# Astable_multivibrator_2021-06-04.net
KiCad netlist of a schematic drawn in EasyEDA
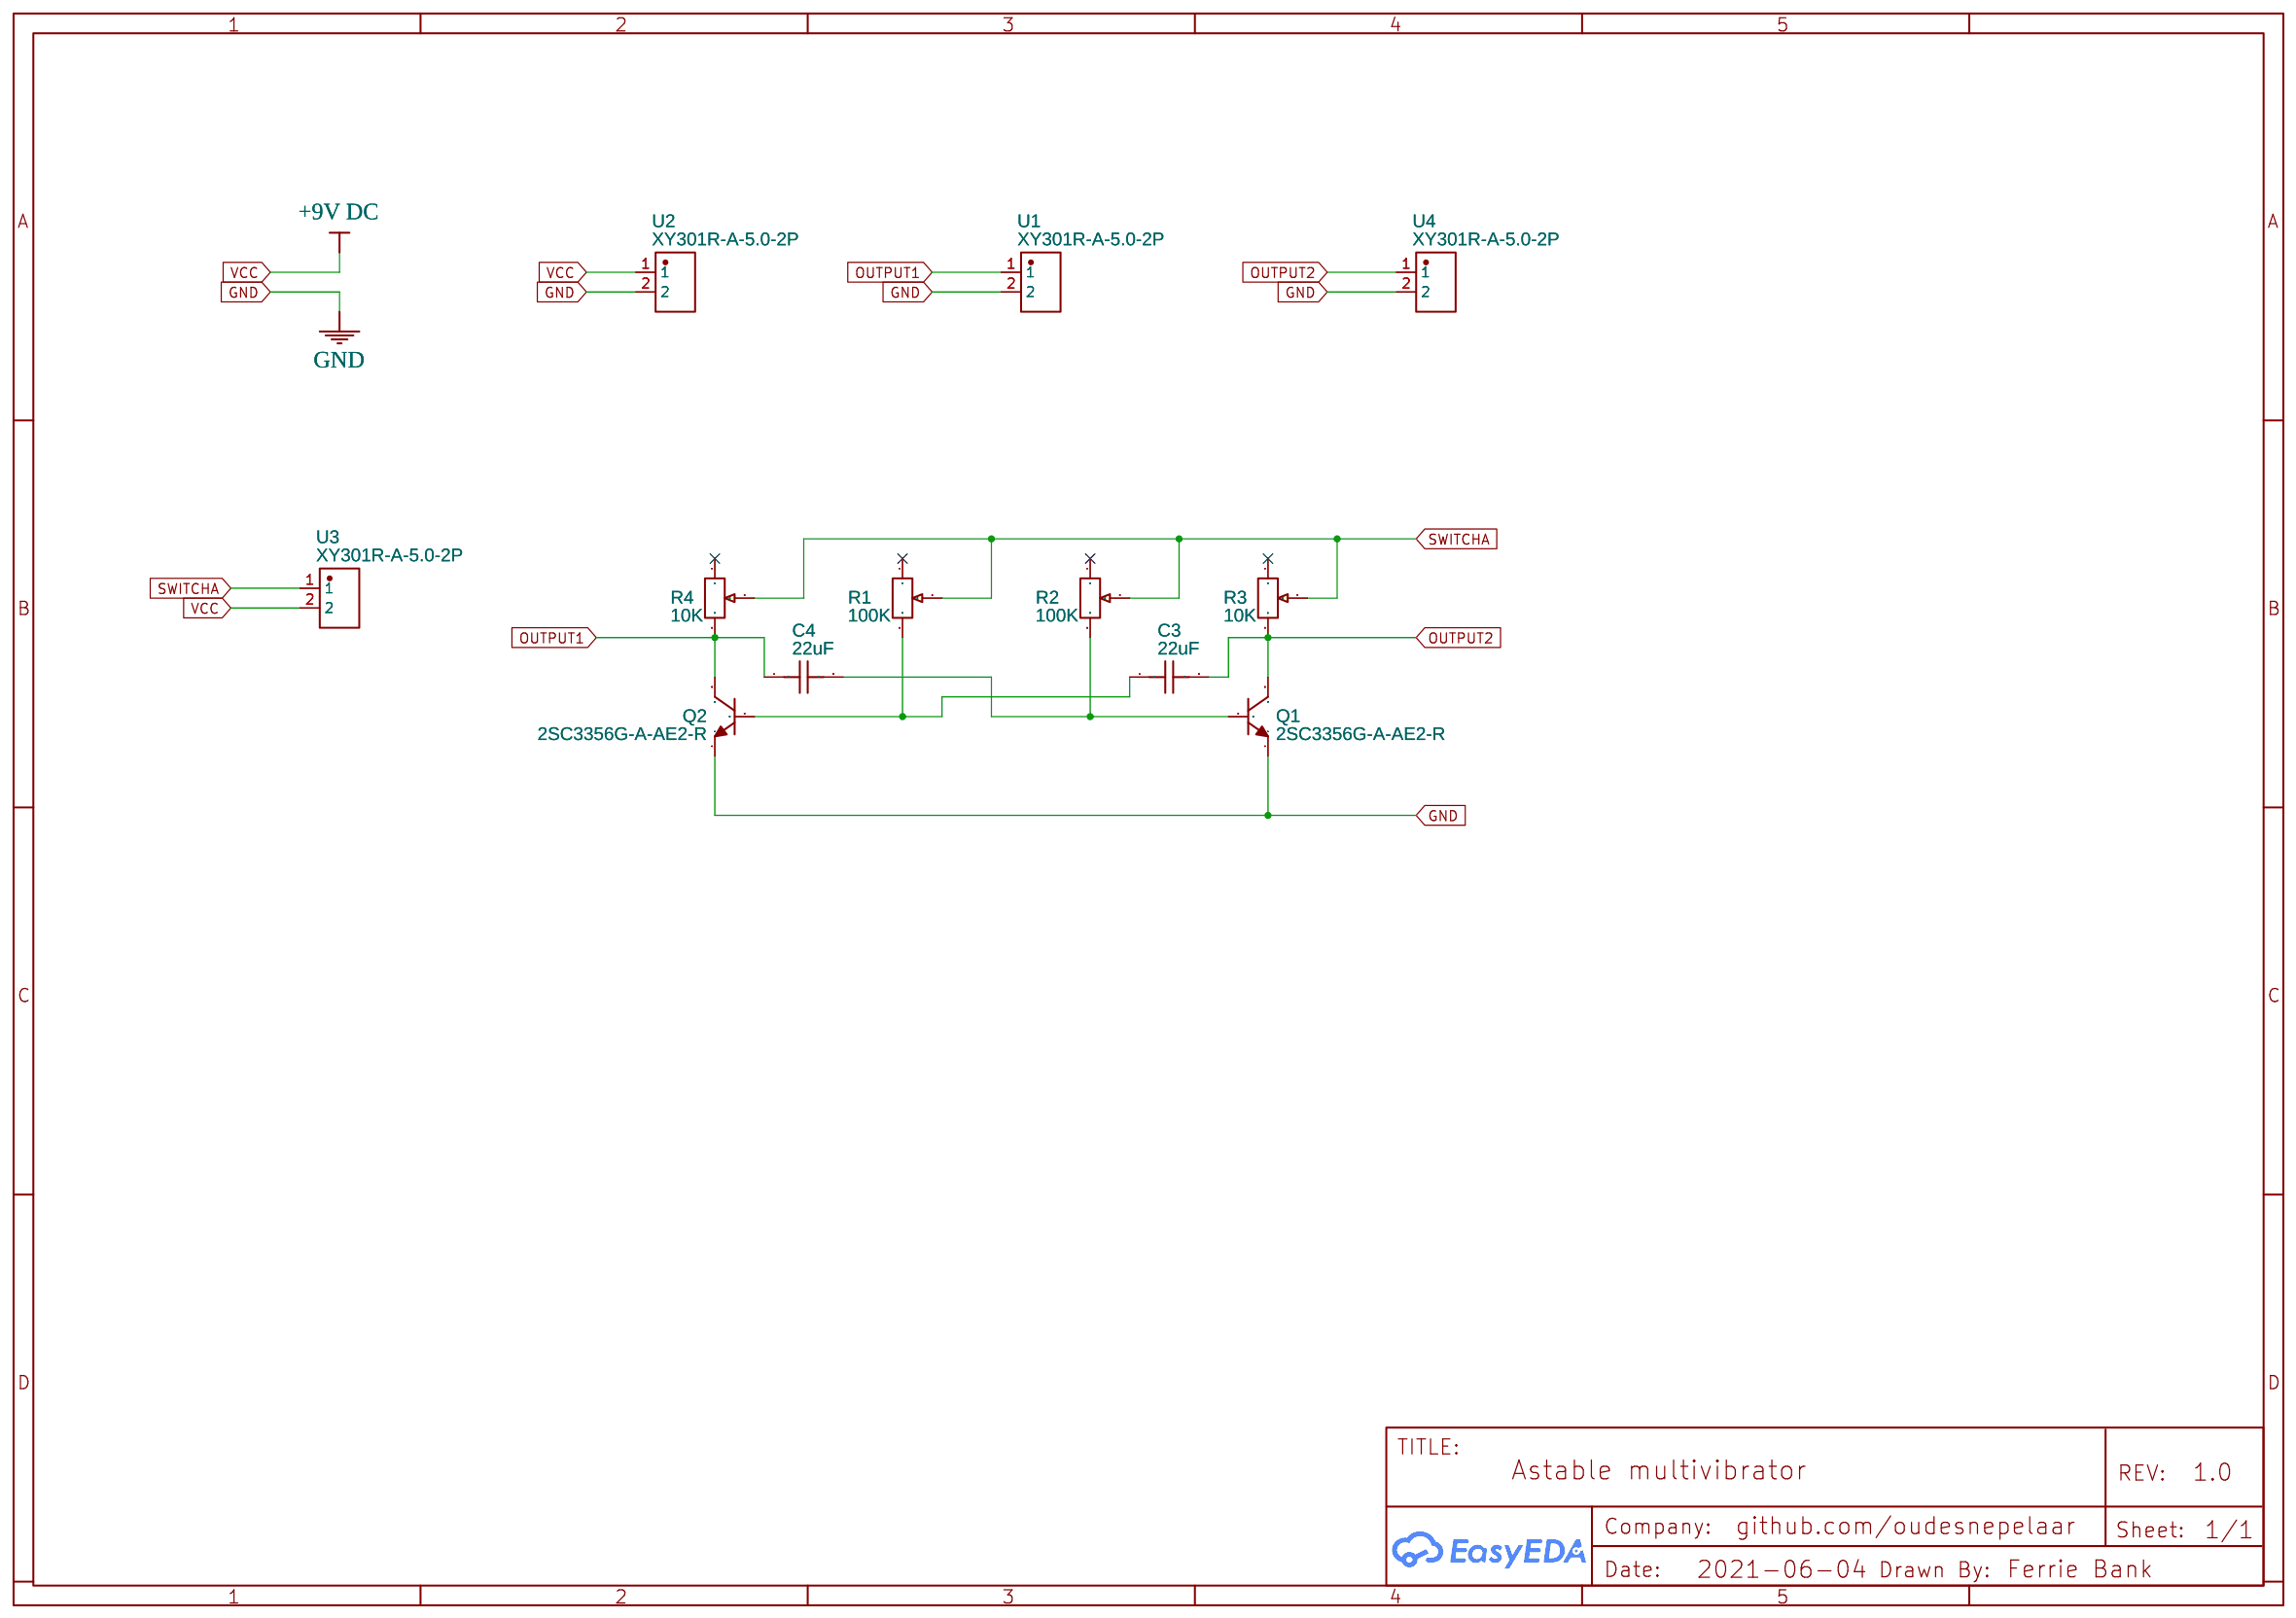
[diagram p0: schematic sheet]

(export (version "E")
  (design (tool "Eeschema 10.0.6"))
  (components
    (comp (ref "C3")
      (value "22uF")
      (fields
        (field (name "BOM_Manufacturer Part") "GRM21BC81C226ME44L")
        (field (name "BOM_Supplier Part") "C258782")
      )
      (libsource (lib "") (part "GRM21BC81C226ME44L"))
    )
    (comp (ref "C4")
      (value "22uF")
      (fields
        (field (name "BOM_Manufacturer Part") "GRM21BC81C226ME44L")
        (field (name "BOM_Supplier Part") "C258782")
      )
      (libsource (lib "") (part "GRM21BC81C226ME44L"))
    )
    (comp (ref "Q1")
      (value "2SC3356G-A-AE2-R")
      (fields (field (name "BOM_Supplier Part") "C171546"))
      (libsource (lib "") (part "2SC3356G-A-AE2-R_1"))
    )
    (comp (ref "Q2")
      (value "2SC3356G-A-AE2-R")
      (fields (field (name "BOM_Supplier Part") "C171546"))
      (libsource (lib "") (part "2SC3356G-A-AE2-R"))
    )
    (comp (ref "R1")
      (value "100K")
      (fields (field (name "BOM_Supplier Part") "C132883"))
      (libsource (lib "") (part "ST-4ETG 100K OHM (104)"))
    )
    (comp (ref "R2")
      (value "100K")
      (fields (field (name "BOM_Supplier Part") "C132883"))
      (libsource (lib "") (part "ST-4ETG 100K OHM (104)"))
    )
    (comp (ref "R3")
      (value "10K")
      (fields (field (name "BOM_Supplier Part") "C132882"))
      (libsource (lib "") (part "ST-4ETG 10K OHM (103)"))
    )
    (comp (ref "R4")
      (value "10K")
      (fields (field (name "BOM_Supplier Part") "C132882"))
      (libsource (lib "") (part "ST-4ETG 10K OHM (103)"))
    )
    (comp (ref "U1")
      (value "XY301R-A-5.0-2P")
      (fields (field (name "BOM_Supplier Part") "C557653"))
      (libsource (lib "") (part "XY301R-A-5.0-2P"))
    )
    (comp (ref "U2")
      (value "XY301R-A-5.0-2P")
      (fields (field (name "BOM_Supplier Part") "C557653"))
      (libsource (lib "") (part "XY301R-A-5.0-2P"))
    )
    (comp (ref "U3")
      (value "XY301R-A-5.0-2P")
      (fields (field (name "BOM_Supplier Part") "C557653"))
      (libsource (lib "") (part "XY301R-A-5.0-2P"))
    )
    (comp (ref "U4")
      (value "XY301R-A-5.0-2P")
      (fields (field (name "BOM_Supplier Part") "C557653"))
      (libsource (lib "") (part "XY301R-A-5.0-2P"))
    )
  )
  (nets
    (net (code "1") (name "GND") (class "Default")
      (node (ref "Q1") (pin "1") (pinfunction "E_1") (pintype "input"))
      (node (ref "Q2") (pin "1") (pinfunction "E_1") (pintype "input"))
      (node (ref "U1") (pin "2") (pinfunction "2_2") (pintype "unspecified"))
      (node (ref "U2") (pin "2") (pinfunction "2_2") (pintype "unspecified"))
      (node (ref "U4") (pin "2") (pinfunction "2_2") (pintype "unspecified"))
    )
    (net (code "2") (name "Net-(Q1-B)") (class "Default")
      (node (ref "C4") (pin "2") (pinfunction "2_2") (pintype "unspecified"))
      (node (ref "Q1") (pin "2") (pinfunction "B_2") (pintype "input"))
      (node (ref "R2") (pin "3") (pinfunction "3_3") (pintype "input"))
    )
    (net (code "3") (name "Net-(Q2-B)") (class "Default")
      (node (ref "C3") (pin "1") (pinfunction "1_1") (pintype "unspecified"))
      (node (ref "Q2") (pin "2") (pinfunction "B_2") (pintype "input"))
      (node (ref "R1") (pin "3") (pinfunction "3_3") (pintype "input"))
    )
    (net (code "4") (name "OUTPUT1") (class "Default")
      (node (ref "C4") (pin "1") (pinfunction "1_1") (pintype "unspecified"))
      (node (ref "Q2") (pin "3") (pinfunction "C_3") (pintype "input"))
      (node (ref "R4") (pin "3") (pinfunction "3_3") (pintype "input"))
      (node (ref "U1") (pin "1") (pinfunction "1_1") (pintype "unspecified"))
    )
    (net (code "5") (name "OUTPUT2") (class "Default")
      (node (ref "C3") (pin "2") (pinfunction "2_2") (pintype "unspecified"))
      (node (ref "Q1") (pin "3") (pinfunction "C_3") (pintype "input"))
      (node (ref "R3") (pin "3") (pinfunction "3_3") (pintype "input"))
      (node (ref "U4") (pin "1") (pinfunction "1_1") (pintype "unspecified"))
    )
    (net (code "6") (name "SWITCHA") (class "Default")
      (node (ref "R1") (pin "2") (pinfunction "2_2") (pintype "input"))
      (node (ref "R2") (pin "2") (pinfunction "2_2") (pintype "input"))
      (node (ref "R3") (pin "2") (pinfunction "2_2") (pintype "input"))
      (node (ref "R4") (pin "2") (pinfunction "2_2") (pintype "input"))
      (node (ref "U3") (pin "1") (pinfunction "1_1") (pintype "unspecified"))
    )
    (net (code "7") (name "VCC") (class "Default")
      (node (ref "U2") (pin "1") (pinfunction "1_1") (pintype "unspecified"))
      (node (ref "U3") (pin "2") (pinfunction "2_2") (pintype "unspecified"))
    )
    (net (code "8") (name "unconnected-(R1-Pad1)") (class "Default")
      (node (ref "R1") (pin "1") (pinfunction "1_1") (pintype "input+no_connect"))
    )
    (net (code "9") (name "unconnected-(R2-Pad1)") (class "Default")
      (node (ref "R2") (pin "1") (pinfunction "1_1") (pintype "input+no_connect"))
    )
    (net (code "10") (name "unconnected-(R3-Pad1)") (class "Default")
      (node (ref "R3") (pin "1") (pinfunction "1_1") (pintype "input+no_connect"))
    )
    (net (code "11") (name "unconnected-(R4-Pad1)") (class "Default")
      (node (ref "R4") (pin "1") (pinfunction "1_1") (pintype "input+no_connect"))
    )
  )
)
